# WLAN_BLUETOOTH.net
KiCad netlist of a schematic drawn in Altium Designer
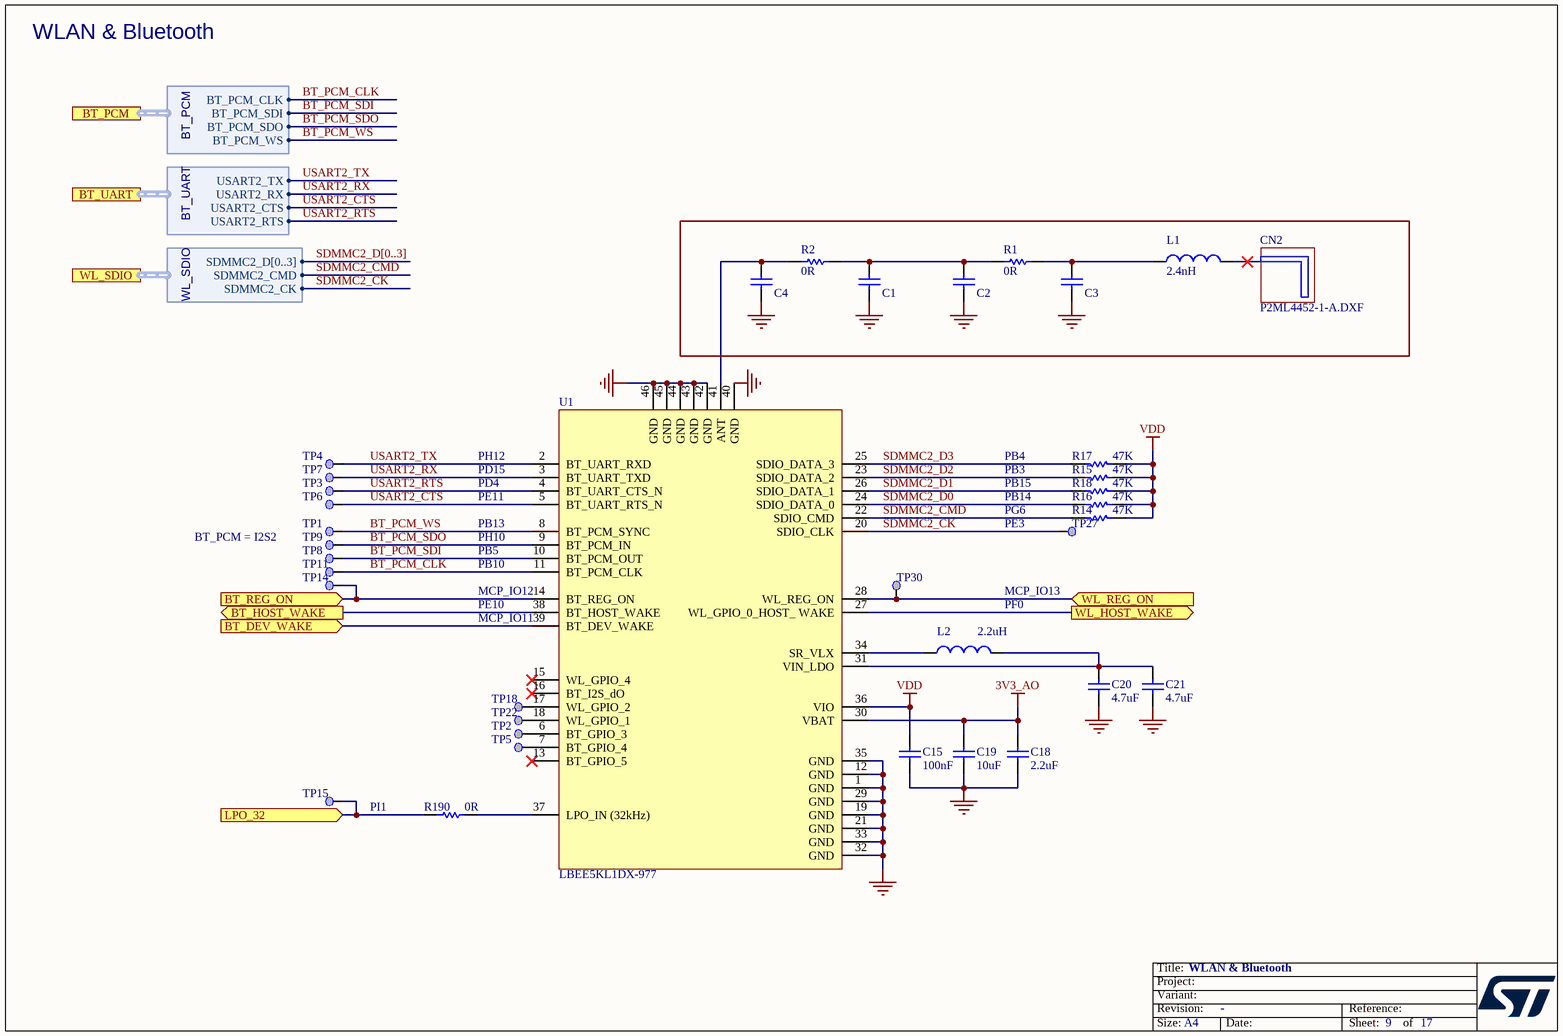
[diagram p0: WLAN_BLUETOOTH.SchDoc]

(export (version "E")
  (design (tool "Eeschema 10.0.6"))
  (components
    (comp (ref "C1")
      (value "Capacitor")
      (footprint "C0402")
      (description "Capacitor, MLCC, 12pF, 50V, NPO, +/-5%, 0402, T=0.5mm")
      (fields
        (field (name "INTERNAL_PART_NUMBER") "MCD-00200")
        (field (name "MANUFACTURER_PART_NUMBER") "CC0402JRNPO9BN120")
      )
      (libsource (lib "MCD_PARTS_database") (part "Capacitor"))
    )
    (comp (ref "C2")
      (value "Capacitor")
      (footprint "C0402")
      (description "Capacitor, MLCC, 12pF, 50V, NPO, +/-5%, 0402, T=0.5mm")
      (fields
        (field (name "INTERNAL_PART_NUMBER") "MCD-00200")
        (field (name "MANUFACTURER_PART_NUMBER") "CC0402JRNPO9BN120")
      )
      (libsource (lib "MCD_PARTS_database") (part "Capacitor"))
    )
    (comp (ref "C3")
      (value "Capacitor")
      (footprint "C0402")
      (description "Capacitor, MLCC, 12pF, 50V, NPO, +/-5%, 0402, T=0.5mm")
      (fields
        (field (name "INTERNAL_PART_NUMBER") "MCD-00200")
        (field (name "MANUFACTURER_PART_NUMBER") "CC0402JRNPO9BN120")
      )
      (libsource (lib "MCD_PARTS_database") (part "Capacitor"))
    )
    (comp (ref "C4")
      (value "Capacitor")
      (footprint "C0402")
      (description "Capacitor, MLCC, 12pF, 50V, NPO, +/-5%, 0402, T=0.5mm")
      (fields
        (field (name "INTERNAL_PART_NUMBER") "MCD-00200")
        (field (name "MANUFACTURER_PART_NUMBER") "CC0402JRNPO9BN120")
      )
      (libsource (lib "MCD_PARTS_database") (part "Capacitor"))
    )
    (comp (ref "C15")
      (value "100nF")
      (footprint "C0402")
      (description "Capacitor, MLCC, 100nF, 16V, X7R, +/-10%, 0402, T=0.5mm")
      (fields
        (field (name "INTERNAL_PART_NUMBER") "MCD-00006")
        (field (name "MANUFACTURER_PART_NUMBER") "CC0402KRX7R7BB104")
      )
      (libsource (lib "MCD_PARTS_database") (part "Capacitor"))
    )
    (comp (ref "C18")
      (value "2.2uF")
      (footprint "C0201_H0P5")
      (description "Capacitor, MLCC, 2.2uF, 10V, X5R,+/-10%, 0201, T=0.5mm")
      (fields
        (field (name "INTERNAL_PART_NUMBER") "MCD-02235")
        (field (name "MANUFACTURER_PART_NUMBER") "GRM033R61A225KE47D")
      )
      (libsource (lib "MCD_PARTS_database") (part "Capacitor"))
    )
    (comp (ref "C19")
      (value "10uF")
      (footprint "C0603")
      (description "Capacitor, MLCC, 10uF, 10V, X5R, +/-10%, 0603, T=0.8mm")
      (fields
        (field (name "INTERNAL_PART_NUMBER") "MCD-00099")
        (field (name "MANUFACTURER_PART_NUMBER") "GRM188R61A106KE69D")
      )
      (libsource (lib "MCD_PARTS_database") (part "Capacitor"))
    )
    (comp (ref "C20")
      (value "4.7uF")
      (footprint "C0402")
      (description "Capacitor, MLCC, 4.7uF, 6V3, X5R, +/-20%, 0402, T=0.5mm")
      (fields
        (field (name "INTERNAL_PART_NUMBER") "MCD-01356")
        (field (name "MANUFACTURER_PART_NUMBER") "GRM155R60J475ME47")
      )
      (libsource (lib "MCD_PARTS_database") (part "Capacitor"))
    )
    (comp (ref "C21")
      (value "4.7uF")
      (footprint "C0402")
      (description "Capacitor, MLCC, 4.7uF, 6V3, X5R, +/-20%, 0402, T=0.5mm")
      (fields
        (field (name "INTERNAL_PART_NUMBER") "MCD-01356")
        (field (name "MANUFACTURER_PART_NUMBER") "GRM155R60J475ME47")
      )
      (libsource (lib "MCD_PARTS_database") (part "Capacitor"))
    )
    (comp (ref "CN2")
      (value "P2ML4452-1-A.DXF")
      (footprint "ANT_MURATA_TYPE-1-DX_P2ML4452-1-A_DXF")
      (description "Murata_Type1DX_AntennaDesign_P2ML4452-1-A.DXF")
      (fields
        (field (name "INTERNAL_PART_NUMBER") "MCD-00656")
        (field (name "MANUFACTURER_PART_NUMBER") "Antenna design")
      )
      (libsource (lib "MCD_PARTS_database") (part "antenna_Wifi_BLE_Murata"))
    )
    (comp (ref "L1")
      (value "2.4nH")
      (footprint "IND_0402_MURATA_LQW15AN2N4C00X")
      (description "Inductor, 2.4nH, +/-0.2nH, Itemp=850mA, 50R, 0402, T=0.6mm, Qmin=20")
      (fields
        (field (name "INTERNAL_PART_NUMBER") "MCD-00657")
        (field (name "MANUFACTURER_PART_NUMBER") "LQW15AN2N4C00#")
      )
      (libsource (lib "MCD_PARTS_database") (part "Inductor"))
    )
    (comp (ref "L2")
      (value "2.2uH")
      (footprint "L0603")
      (description "Inductor, 2.2uH, +/-20%, 1050mA, 0R2, 0603, T=1mm")
      (fields
        (field (name "INTERNAL_PART_NUMBER") "MCD-00659")
        (field (name "MANUFACTURER_PART_NUMBER") "LQM18PN2R2MGH")
      )
      (libsource (lib "MCD_PARTS_database") (part "Inductor"))
    )
    (comp (ref "R1")
      (value "0R")
      (footprint "R0402")
      (description "Resistor, 0R, 0402, +/-5%, 1/16W")
      (fields
        (field (name "INTERNAL_PART_NUMBER") "MCD-00052")
        (field (name "MANUFACTURER_PART_NUMBER") "RC0402JR-070RL")
      )
      (libsource (lib "MCD_PARTS_database") (part "Resistor"))
    )
    (comp (ref "R2")
      (value "0R")
      (footprint "R0402")
      (description "Resistor, 0R, 0402, +/-5%, 1/16W")
      (fields
        (field (name "INTERNAL_PART_NUMBER") "MCD-00052")
        (field (name "MANUFACTURER_PART_NUMBER") "RC0402JR-070RL")
      )
      (libsource (lib "MCD_PARTS_database") (part "Resistor"))
    )
    (comp (ref "R14")
      (value "47K")
      (footprint "R0402")
      (description "Resistor, 47K, 0402, +/-1%, 1/16W")
      (fields
        (field (name "INTERNAL_PART_NUMBER") "MCD-00063")
        (field (name "MANUFACTURER_PART_NUMBER") "RC0402FR-0747KL")
      )
      (libsource (lib "MCD_PARTS_database") (part "Resistor"))
    )
    (comp (ref "R15")
      (value "47K")
      (footprint "R0402")
      (description "Resistor, 47K, 0402, +/-1%, 1/16W")
      (fields
        (field (name "INTERNAL_PART_NUMBER") "MCD-00063")
        (field (name "MANUFACTURER_PART_NUMBER") "RC0402FR-0747KL")
      )
      (libsource (lib "MCD_PARTS_database") (part "Resistor"))
    )
    (comp (ref "R16")
      (value "47K")
      (footprint "R0402")
      (description "Resistor, 47K, 0402, +/-1%, 1/16W")
      (fields
        (field (name "INTERNAL_PART_NUMBER") "MCD-00063")
        (field (name "MANUFACTURER_PART_NUMBER") "RC0402FR-0747KL")
      )
      (libsource (lib "MCD_PARTS_database") (part "Resistor"))
    )
    (comp (ref "R17")
      (value "47K")
      (footprint "R0402")
      (description "Resistor, 47K, 0402, +/-1%, 1/16W")
      (fields
        (field (name "INTERNAL_PART_NUMBER") "MCD-00063")
        (field (name "MANUFACTURER_PART_NUMBER") "RC0402FR-0747KL")
      )
      (libsource (lib "MCD_PARTS_database") (part "Resistor"))
    )
    (comp (ref "R18")
      (value "47K")
      (footprint "R0402")
      (description "Resistor, 47K, 0402, +/-1%, 1/16W")
      (fields
        (field (name "INTERNAL_PART_NUMBER") "MCD-00063")
        (field (name "MANUFACTURER_PART_NUMBER") "RC0402FR-0747KL")
      )
      (libsource (lib "MCD_PARTS_database") (part "Resistor"))
    )
    (comp (ref "R190")
      (value "0R")
      (footprint "R0402")
      (description "Resistor, 0R, 0402, +/-5%, 1/16W")
      (fields (field (name "INTERNAL_PART_NUMBER") "MCD-00052") (field (name "MANUFACTURER") "YAGEO"))
      (libsource (lib "MCD_PARTS_database") (part "Resistor"))
    )
    (comp (ref "TP1")
      (value "Test Point")
      (footprint "TP_SMD_1MM")
      (description "Test Point 1mm")
      (fields (field (name "INTERNAL_PART_NUMBER") "MCD-00074"))
      (libsource (lib "MCD_PARTS_database") (part "Test Point"))
    )
    (comp (ref "TP2")
      (value "Test Point")
      (footprint "TP_SMD_1MM")
      (description "Test Point 1mm")
      (fields (field (name "INTERNAL_PART_NUMBER") "MCD-00074"))
      (libsource (lib "MCD_PARTS_database") (part "Test Point"))
    )
    (comp (ref "TP3")
      (value "Test Point")
      (footprint "TP_SMD_1MM")
      (description "Test Point 1mm")
      (fields (field (name "INTERNAL_PART_NUMBER") "MCD-00074"))
      (libsource (lib "MCD_PARTS_database") (part "Test Point"))
    )
    (comp (ref "TP4")
      (value "Test Point")
      (footprint "TP_SMD_1MM")
      (description "Test Point 1mm")
      (fields (field (name "INTERNAL_PART_NUMBER") "MCD-00074"))
      (libsource (lib "MCD_PARTS_database") (part "Test Point"))
    )
    (comp (ref "TP5")
      (value "Test Point")
      (footprint "TP_SMD_1MM")
      (description "Test Point 1mm")
      (fields (field (name "INTERNAL_PART_NUMBER") "MCD-00074"))
      (libsource (lib "MCD_PARTS_database") (part "Test Point"))
    )
    (comp (ref "TP6")
      (value "Test Point")
      (footprint "TP_SMD_1MM")
      (description "Test Point 1mm")
      (fields (field (name "INTERNAL_PART_NUMBER") "MCD-00074"))
      (libsource (lib "MCD_PARTS_database") (part "Test Point"))
    )
    (comp (ref "TP7")
      (value "Test Point")
      (footprint "TP_SMD_1MM")
      (description "Test Point 1mm")
      (fields (field (name "INTERNAL_PART_NUMBER") "MCD-00074"))
      (libsource (lib "MCD_PARTS_database") (part "Test Point"))
    )
    (comp (ref "TP8")
      (value "Test Point")
      (footprint "TP_SMD_1MM")
      (description "Test Point 1mm")
      (fields (field (name "INTERNAL_PART_NUMBER") "MCD-00074"))
      (libsource (lib "MCD_PARTS_database") (part "Test Point"))
    )
    (comp (ref "TP9")
      (value "Test Point")
      (footprint "TP_SMD_1MM")
      (description "Test Point 1mm")
      (fields (field (name "INTERNAL_PART_NUMBER") "MCD-00074"))
      (libsource (lib "MCD_PARTS_database") (part "Test Point"))
    )
    (comp (ref "TP11")
      (value "Test Point")
      (footprint "TP_SMD_1MM")
      (description "Test Point 1mm")
      (fields (field (name "INTERNAL_PART_NUMBER") "MCD-00074"))
      (libsource (lib "MCD_PARTS_database") (part "Test Point"))
    )
    (comp (ref "TP14")
      (value "Test Point")
      (footprint "TP_SMD_1MM")
      (description "Test Point 1mm")
      (fields (field (name "INTERNAL_PART_NUMBER") "MCD-00074"))
      (libsource (lib "MCD_PARTS_database") (part "Test Point"))
    )
    (comp (ref "TP15")
      (value "Test Point")
      (footprint "TP_SMD_1MM")
      (description "Test Point 1mm")
      (fields (field (name "INTERNAL_PART_NUMBER") "MCD-00074"))
      (libsource (lib "MCD_PARTS_database") (part "Test Point"))
    )
    (comp (ref "TP18")
      (value "Test Point")
      (footprint "TP_SMD_1MM")
      (description "Test Point 1mm")
      (fields (field (name "INTERNAL_PART_NUMBER") "MCD-00074"))
      (libsource (lib "MCD_PARTS_database") (part "Test Point"))
    )
    (comp (ref "TP22")
      (value "Test Point")
      (footprint "TP_SMD_1MM")
      (description "Test Point 1mm")
      (fields (field (name "INTERNAL_PART_NUMBER") "MCD-00074"))
      (libsource (lib "MCD_PARTS_database") (part "Test Point"))
    )
    (comp (ref "TP27")
      (value "Test Point")
      (footprint "TP_SMD_1MM")
      (description "Test Point 1mm")
      (fields (field (name "INTERNAL_PART_NUMBER") "MCD-00074"))
      (libsource (lib "") (part "Test Point_1"))
    )
    (comp (ref "TP30")
      (value "Test Point")
      (footprint "TP_SMD_1MM")
      (description "Test Point 1mm")
      (fields (field (name "INTERNAL_PART_NUMBER") "MCD-00074"))
      (libsource (lib "") (part "Test Point_2"))
    )
    (comp (ref "U1")
      (value "LBEE5KL1DX-977")
      (footprint "MOD_WLAN-BT_MURATA_LBEE5KL1DX-883")
      (description "IEEE802.11b/g/n W-LAN + Bluetooth 4.1+EDR module")
      (fields (field (name "INTERNAL_PART_NUMBER") "MCD-00268") (field (name "MANUFACTURER") "MURATA"))
      (libsource (lib "MCD_PARTS_database") (part "LBEE5KL1DX-883"))
    )
  )
  (nets
    (net (code "4") (name "/BT_DEV_WAKE") (class "Default")
      (node (ref "U1") (pin "39") (pinfunction "BT_DEV_WAKE_39") (pintype "passive"))
    )
    (net (code "5") (name "/BT_HOST_WAKE") (class "Default")
      (node (ref "U1") (pin "38") (pinfunction "BT_HOST_WAKE_38") (pintype "passive"))
    )
    (net (code "6") (name "/BT_PCM_CLK") (class "Default")
      (node (ref "TP11") (pin "1") (pinfunction "1_1") (pintype "passive"))
      (node (ref "U1") (pin "11") (pinfunction "BT_PCM_CLK_11") (pintype "passive"))
    )
    (net (code "7") (name "/BT_PCM_SDI") (class "Default")
      (node (ref "TP8") (pin "1") (pinfunction "1_1") (pintype "passive"))
      (node (ref "U1") (pin "10") (pinfunction "BT_PCM_OUT_10") (pintype "passive"))
    )
    (net (code "8") (name "/BT_PCM_SDO") (class "Default")
      (node (ref "TP9") (pin "1") (pinfunction "1_1") (pintype "passive"))
      (node (ref "U1") (pin "9") (pinfunction "BT_PCM_IN_9") (pintype "passive"))
    )
    (net (code "9") (name "/BT_PCM_WS") (class "Default")
      (node (ref "TP1") (pin "1") (pinfunction "1_1") (pintype "passive"))
      (node (ref "U1") (pin "8") (pinfunction "BT_PCM_SYNC_8") (pintype "passive"))
    )
    (net (code "10") (name "/BT_REG_ON") (class "Default")
      (node (ref "TP14") (pin "1") (pinfunction "1_1") (pintype "passive"))
      (node (ref "U1") (pin "14") (pinfunction "BT_REG_ON_14") (pintype "passive"))
    )
    (net (code "11") (name "/LPO_32") (class "Default")
      (node (ref "R190") (pin "1") (pinfunction "1_1") (pintype "passive"))
      (node (ref "TP15") (pin "1") (pinfunction "1_1") (pintype "passive"))
    )
    (net (code "12") (name "/SDMMC2_CK") (class "Default")
      (node (ref "TP27") (pin "1") (pinfunction "1_1") (pintype "passive"))
      (node (ref "U1") (pin "20") (pinfunction "SDIO_CLK_20") (pintype "passive"))
    )
    (net (code "13") (name "/SDMMC2_CMD") (class "Default")
      (node (ref "R14") (pin "2") (pinfunction "2_2") (pintype "passive"))
      (node (ref "U1") (pin "22") (pinfunction "SDIO_CMD_22") (pintype "passive"))
    )
    (net (code "14") (name "/SDMMC2_D0") (class "Default")
      (node (ref "R16") (pin "2") (pinfunction "2_2") (pintype "passive"))
      (node (ref "U1") (pin "24") (pinfunction "SDIO_DATA_0_24") (pintype "passive"))
    )
    (net (code "15") (name "/SDMMC2_D1") (class "Default")
      (node (ref "R18") (pin "2") (pinfunction "2_2") (pintype "passive"))
      (node (ref "U1") (pin "26") (pinfunction "SDIO_DATA_1_26") (pintype "passive"))
    )
    (net (code "16") (name "/SDMMC2_D2") (class "Default")
      (node (ref "R15") (pin "2") (pinfunction "2_2") (pintype "passive"))
      (node (ref "U1") (pin "23") (pinfunction "SDIO_DATA_2_23") (pintype "passive"))
    )
    (net (code "17") (name "/SDMMC2_D3") (class "Default")
      (node (ref "R17") (pin "2") (pinfunction "2_2") (pintype "passive"))
      (node (ref "U1") (pin "25") (pinfunction "SDIO_DATA_3_25") (pintype "passive"))
    )
    (net (code "18") (name "/USART2_CTS") (class "Default")
      (node (ref "TP6") (pin "1") (pinfunction "1_1") (pintype "passive"))
      (node (ref "U1") (pin "5") (pinfunction "BT_UART_RTS_N_5") (pintype "passive"))
    )
    (net (code "19") (name "/USART2_RTS") (class "Default")
      (node (ref "TP3") (pin "1") (pinfunction "1_1") (pintype "passive"))
      (node (ref "U1") (pin "4") (pinfunction "BT_UART_CTS_N_4") (pintype "passive"))
    )
    (net (code "20") (name "/USART2_RX") (class "Default")
      (node (ref "TP7") (pin "1") (pinfunction "1_1") (pintype "passive"))
      (node (ref "U1") (pin "3") (pinfunction "BT_UART_TXD_3") (pintype "passive"))
    )
    (net (code "21") (name "/USART2_TX") (class "Default")
      (node (ref "TP4") (pin "1") (pinfunction "1_1") (pintype "passive"))
      (node (ref "U1") (pin "2") (pinfunction "BT_UART_RXD_2") (pintype "passive"))
    )
    (net (code "22") (name "/WL_HOST_WAKE") (class "Default")
      (node (ref "U1") (pin "27") (pinfunction "WL_GPIO_0_HOST__WAKE_27") (pintype "passive"))
    )
    (net (code "23") (name "/WL_REG_ON") (class "Default")
      (node (ref "TP30") (pin "1") (pinfunction "1_1") (pintype "passive"))
      (node (ref "U1") (pin "28") (pinfunction "WL_REG_ON_28") (pintype "passive"))
    )
    (net (code "28") (name "3V3_AO") (class "Default")
      (node (ref "C18") (pin "2") (pinfunction "2_2") (pintype "passive"))
      (node (ref "C19") (pin "2") (pinfunction "2_2") (pintype "passive"))
      (node (ref "U1") (pin "30") (pinfunction "VBAT_30") (pintype "passive"))
    )
    (net (code "29") (name "GND") (class "Default")
      (node (ref "C1") (pin "1") (pinfunction "1_1") (pintype "passive"))
      (node (ref "C15") (pin "1") (pinfunction "1_1") (pintype "passive"))
      (node (ref "C18") (pin "1") (pinfunction "1_1") (pintype "passive"))
      (node (ref "C19") (pin "1") (pinfunction "1_1") (pintype "passive"))
      (node (ref "C2") (pin "1") (pinfunction "1_1") (pintype "passive"))
      (node (ref "C20") (pin "1") (pinfunction "1_1") (pintype "passive"))
      (node (ref "C21") (pin "1") (pinfunction "1_1") (pintype "passive"))
      (node (ref "C3") (pin "1") (pinfunction "1_1") (pintype "passive"))
      (node (ref "C4") (pin "1") (pinfunction "1_1") (pintype "passive"))
      (node (ref "U1") (pin "1") (pinfunction "GND_1") (pintype "passive"))
      (node (ref "U1") (pin "12") (pinfunction "GND_12") (pintype "passive"))
      (node (ref "U1") (pin "19") (pinfunction "GND_19") (pintype "passive"))
      (node (ref "U1") (pin "21") (pinfunction "GND_21") (pintype "passive"))
      (node (ref "U1") (pin "29") (pinfunction "GND_29") (pintype "passive"))
      (node (ref "U1") (pin "32") (pinfunction "GND_32") (pintype "passive"))
      (node (ref "U1") (pin "33") (pinfunction "GND_33") (pintype "passive"))
      (node (ref "U1") (pin "35") (pinfunction "GND_35") (pintype "passive"))
      (node (ref "U1") (pin "40") (pinfunction "GND_40") (pintype "passive"))
      (node (ref "U1") (pin "42") (pinfunction "GND_42") (pintype "passive"))
      (node (ref "U1") (pin "43") (pinfunction "GND_43") (pintype "passive"))
      (node (ref "U1") (pin "44") (pinfunction "GND_44") (pintype "passive"))
      (node (ref "U1") (pin "45") (pinfunction "GND_45") (pintype "passive"))
      (node (ref "U1") (pin "46") (pinfunction "GND_46") (pintype "passive"))
    )
    (net (code "30") (name "Net-(C1-Pad2)") (class "Default")
      (node (ref "C1") (pin "2") (pinfunction "2_2") (pintype "passive"))
      (node (ref "C2") (pin "2") (pinfunction "2_2") (pintype "passive"))
      (node (ref "R1") (pin "2") (pinfunction "2_2") (pintype "passive"))
      (node (ref "R2") (pin "1") (pinfunction "1_1") (pintype "passive"))
    )
    (net (code "31") (name "Net-(C3-Pad2)") (class "Default")
      (node (ref "C3") (pin "2") (pinfunction "2_2") (pintype "passive"))
      (node (ref "L1") (pin "1") (pinfunction "1_1") (pintype "passive"))
      (node (ref "R1") (pin "1") (pinfunction "1_1") (pintype "passive"))
    )
    (net (code "32") (name "Net-(U1-ANT)") (class "Default")
      (node (ref "C4") (pin "2") (pinfunction "2_2") (pintype "passive"))
      (node (ref "R2") (pin "2") (pinfunction "2_2") (pintype "passive"))
      (node (ref "U1") (pin "41") (pinfunction "ANT_41") (pintype "passive"))
    )
    (net (code "33") (name "Net-(U1-BT_GPIO_3)") (class "Default")
      (node (ref "TP2") (pin "1") (pinfunction "1_1") (pintype "passive"))
      (node (ref "U1") (pin "6") (pinfunction "BT_GPIO_3_6") (pintype "passive"))
    )
    (net (code "34") (name "Net-(U1-BT_GPIO_4)") (class "Default")
      (node (ref "TP5") (pin "1") (pinfunction "1_1") (pintype "passive"))
      (node (ref "U1") (pin "7") (pinfunction "BT_GPIO_4_7") (pintype "passive"))
    )
    (net (code "35") (name "Net-(U1-LPO_IN_(32kHz))") (class "Default")
      (node (ref "R190") (pin "2") (pinfunction "2_2") (pintype "passive"))
      (node (ref "U1") (pin "37") (pinfunction "LPO_IN_(32kHz)_37") (pintype "passive"))
    )
    (net (code "36") (name "Net-(U1-SR_VLX)") (class "Default")
      (node (ref "L2") (pin "1") (pinfunction "1_1") (pintype "passive"))
      (node (ref "U1") (pin "34") (pinfunction "SR_VLX_34") (pintype "passive"))
    )
    (net (code "37") (name "Net-(U1-VIN_LDO)") (class "Default")
      (node (ref "C20") (pin "2") (pinfunction "2_2") (pintype "passive"))
      (node (ref "C21") (pin "2") (pinfunction "2_2") (pintype "passive"))
      (node (ref "L2") (pin "2") (pinfunction "2_2") (pintype "passive"))
      (node (ref "U1") (pin "31") (pinfunction "VIN_LDO_31") (pintype "passive"))
    )
    (net (code "38") (name "Net-(U1-WL_GPIO_1)") (class "Default")
      (node (ref "TP22") (pin "1") (pinfunction "1_1") (pintype "passive"))
      (node (ref "U1") (pin "18") (pinfunction "WL_GPIO_1_18") (pintype "passive"))
    )
    (net (code "39") (name "Net-(U1-WL_GPIO_2)") (class "Default")
      (node (ref "TP18") (pin "1") (pinfunction "1_1") (pintype "passive"))
      (node (ref "U1") (pin "17") (pinfunction "WL_GPIO_2_17") (pintype "passive"))
    )
    (net (code "40") (name "VDD") (class "Default")
      (node (ref "C15") (pin "2") (pinfunction "2_2") (pintype "passive"))
      (node (ref "R14") (pin "1") (pinfunction "1_1") (pintype "passive"))
      (node (ref "R15") (pin "1") (pinfunction "1_1") (pintype "passive"))
      (node (ref "R16") (pin "1") (pinfunction "1_1") (pintype "passive"))
      (node (ref "R17") (pin "1") (pinfunction "1_1") (pintype "passive"))
      (node (ref "R18") (pin "1") (pinfunction "1_1") (pintype "passive"))
      (node (ref "U1") (pin "36") (pinfunction "VIO_36") (pintype "passive"))
    )
    (net (code "41") (name "unconnected-(L1-Pad2)") (class "Default")
      (node (ref "L1") (pin "2") (pinfunction "2_2") (pintype "passive"))
    )
    (net (code "42") (name "unconnected-(U1-BT_GPIO_5-Pad13)") (class "Default")
      (node (ref "U1") (pin "13") (pinfunction "BT_GPIO_5_13") (pintype "passive+no_connect"))
    )
    (net (code "43") (name "unconnected-(U1-BT_I2S_dO-Pad16)") (class "Default")
      (node (ref "U1") (pin "16") (pinfunction "BT_I2S_dO_16") (pintype "passive+no_connect"))
    )
    (net (code "44") (name "unconnected-(U1-WL_GPIO_4-Pad15)") (class "Default")
      (node (ref "U1") (pin "15") (pinfunction "WL_GPIO_4_15") (pintype "passive+no_connect"))
    )
  )
)
